# Filter_Capacitors_-_I2C.net
KiCad netlist of a schematic drawn in Altium Designer
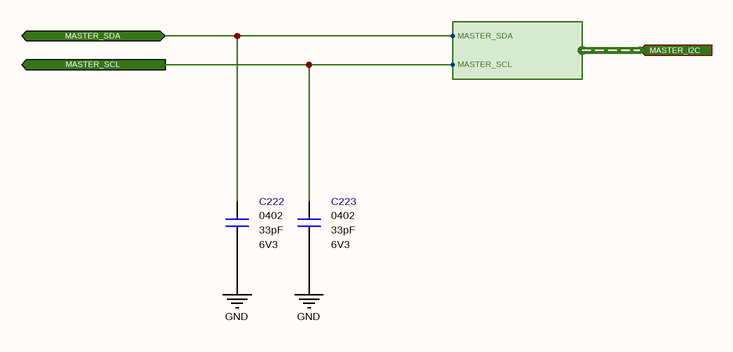
[diagram p0: Filter Capacitors - I2C.SchDoc]

(export (version "E")
  (design (tool "Eeschema 10.0.6"))
  (components
    (comp (ref "C222")
      (value "33pF")
      (footprint "CAPACITOR_0402")
      (description "Capacitor - 33pF [0402] (Ceramic)")
      (fields
        (field (name "TOLERANCE") "10%")
        (field (name "CASE") "0402")
        (field (name "VOLTAGE") "6V3")
        (field (name "MANUFACTURER PART NUMBER") "C0402C330J9RACAUTO")
      )
      (libsource (lib "Ovoo_Library") (part "Capacitor - 33pF [0402-6V3]"))
    )
    (comp (ref "C223")
      (value "33pF")
      (footprint "CAPACITOR_0402")
      (description "Capacitor - 33pF [0402] (Ceramic)")
      (fields
        (field (name "TOLERANCE") "10%")
        (field (name "CASE") "0402")
        (field (name "VOLTAGE") "6V3")
        (field (name "MANUFACTURER PART NUMBER") "C0402C330J9RACAUTO")
      )
      (libsource (lib "Ovoo_Library") (part "Capacitor - 33pF [0402-6V3]"))
    )
  )
  (nets
    (net (code "2") (name "/MASTER_SCL") (class "Default")
      (node (ref "C223") (pin "2") (pinfunction "2_2") (pintype "passive"))
    )
    (net (code "3") (name "/MASTER_SDA") (class "Default")
      (node (ref "C222") (pin "2") (pinfunction "2_2") (pintype "passive"))
    )
    (net (code "5") (name "GND") (class "Default")
      (node (ref "C222") (pin "1") (pinfunction "1_1") (pintype "passive"))
      (node (ref "C223") (pin "1") (pinfunction "1_1") (pintype "passive"))
    )
  )
)
